# TeamB_PDS_Schematic_new.net
KiCad netlist of a schematic drawn in EAGLE
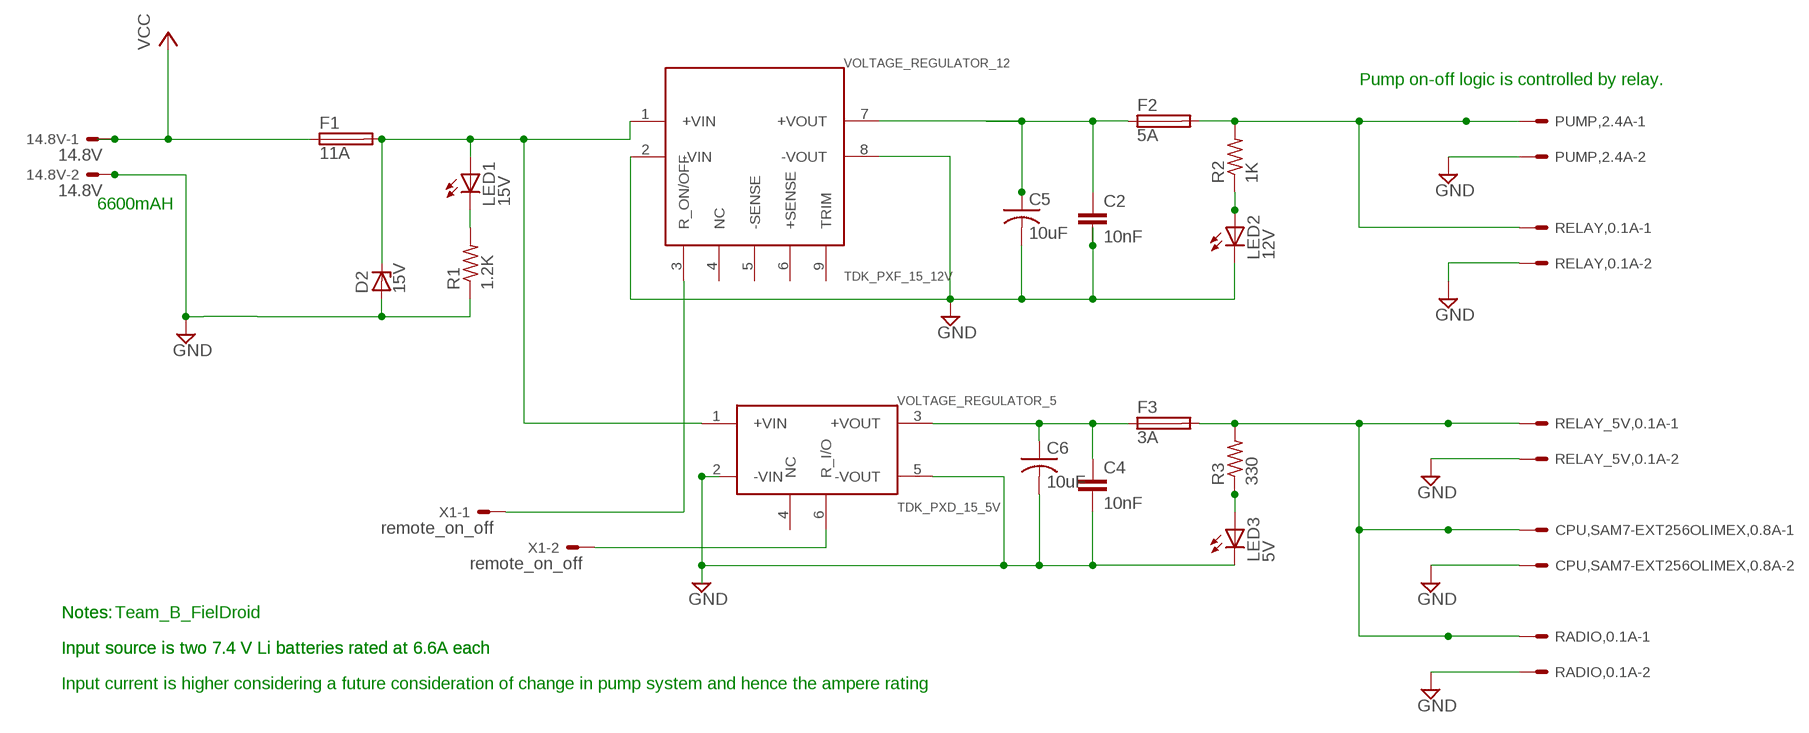
[diagram p0: schematic, sheet 1]

(export (version "E")
  (design (tool "Eeschema 10.0.6"))
  (components
    (comp (ref "14.8V")
      (value "14.8V")
      (footprint "eagle-import:5566-2")
      (libsource (lib "eagle-import") (part "5566-2"))
    )
    (comp (ref "C2")
      (value "10nF")
      (footprint "eagle-import:C2.5-4")
      (libsource (lib "eagle-import") (part "C2.5/4"))
    )
    (comp (ref "C4")
      (value "10nF")
      (footprint "eagle-import:C2.5-4")
      (libsource (lib "eagle-import") (part "C2.5/4"))
    )
    (comp (ref "C5")
      (value "10uF")
      (footprint "eagle-import:C050-045X075")
      (libsource (lib "eagle-import") (part "C-US050-045X075"))
    )
    (comp (ref "C6")
      (value "10uF")
      (footprint "eagle-import:C050-045X075")
      (libsource (lib "eagle-import") (part "C-US050-045X075"))
    )
    (comp (ref "CPU,SAM7-EXT256OLIMEX,0.8A")
      (value "5566-2")
      (footprint "eagle-import:5566-2")
      (libsource (lib "eagle-import") (part "5566-2"))
    )
    (comp (ref "D2")
      (value "15V")
      (footprint "eagle-import:DO41Z10")
      (libsource (lib "eagle-import") (part "1N4728"))
    )
    (comp (ref "F1")
      (value "11A")
      (footprint "eagle-import:FUSE_HOLDER_5X20MM")
      (libsource (lib "eagle-import") (part "FUSEBLANK_5X20MM"))
    )
    (comp (ref "F2")
      (value "5A")
      (footprint "eagle-import:FUSE_HOLDER_5X20MM")
      (libsource (lib "eagle-import") (part "FUSEBLANK_5X20MM"))
    )
    (comp (ref "F3")
      (value "3A")
      (footprint "eagle-import:FUSE_HOLDER_5X20MM")
      (libsource (lib "eagle-import") (part "FUSEBLANK_5X20MM"))
    )
    (comp (ref "LED1")
      (value "15V")
      (footprint "eagle-import:LED5MM")
      (libsource (lib "eagle-import") (part "LED5MM"))
    )
    (comp (ref "LED2")
      (value "12V")
      (footprint "eagle-import:LED5MM")
      (libsource (lib "eagle-import") (part "LED5MM"))
    )
    (comp (ref "LED3")
      (value "5V")
      (footprint "eagle-import:LED5MM")
      (libsource (lib "eagle-import") (part "LED5MM"))
    )
    (comp (ref "PUMP,2.4A")
      (value "5566-2")
      (footprint "eagle-import:5566-2")
      (libsource (lib "eagle-import") (part "5566-2"))
    )
    (comp (ref "R1")
      (value "1.2K")
      (footprint "eagle-import:0309_12")
      (libsource (lib "eagle-import") (part "R-US_0309/12"))
    )
    (comp (ref "R2")
      (value "1K")
      (footprint "eagle-import:0309_12")
      (libsource (lib "eagle-import") (part "R-US_0309/12"))
    )
    (comp (ref "R3")
      (value "330")
      (footprint "eagle-import:0309_12")
      (libsource (lib "eagle-import") (part "R-US_0309/12"))
    )
    (comp (ref "RADIO,0.1A")
      (value "5566-2")
      (footprint "eagle-import:5566-2")
      (libsource (lib "eagle-import") (part "5566-2"))
    )
    (comp (ref "RELAY,0.1A")
      (value "5566-2")
      (footprint "eagle-import:5566-2")
      (libsource (lib "eagle-import") (part "5566-2"))
    )
    (comp (ref "RELAY_5V,0.1A")
      (value "5566-2")
      (footprint "eagle-import:5566-2")
      (libsource (lib "eagle-import") (part "5566-2"))
    )
    (comp (ref "VOLTAGE_REGULATOR_5")
      (value "TDK_PXD_15_5V")
      (footprint "eagle-import:TDK-PXD_15-5V")
      (libsource (lib "eagle-import") (part "TDK_PXD_15_5V"))
    )
    (comp (ref "VOLTAGE_REGULATOR_12")
      (value "TDK_PXF_15_12V")
      (footprint "eagle-import:TDK_PXF_15_12V")
      (libsource (lib "eagle-import") (part "TDK_PXF_15_12V"))
    )
    (comp (ref "X1")
      (value "remote_on_off")
      (footprint "eagle-import:5566-2")
      (libsource (lib "eagle-import") (part "5566-2"))
    )
  )
  (nets
    (net (code "1") (name "GND") (class "Default")
      (node (ref "14.8V") (pin "2") (pinfunction "S_2") (pintype "passive"))
      (node (ref "C2") (pin "2") (pinfunction "2_2") (pintype "passive"))
      (node (ref "C4") (pin "2") (pinfunction "2_2") (pintype "passive"))
      (node (ref "C5") (pin "2") (pinfunction "2_2") (pintype "passive"))
      (node (ref "C6") (pin "2") (pinfunction "2_2") (pintype "passive"))
      (node (ref "CPU,SAM7-EXT256OLIMEX,0.8A") (pin "2") (pinfunction "S_2") (pintype "passive"))
      (node (ref "D2") (pin "A") (pinfunction "A_A") (pintype "passive"))
      (node (ref "LED2") (pin "K") (pinfunction "C_K") (pintype "passive"))
      (node (ref "LED3") (pin "K") (pinfunction "C_K") (pintype "passive"))
      (node (ref "PUMP,2.4A") (pin "2") (pinfunction "S_2") (pintype "passive"))
      (node (ref "R1") (pin "1") (pinfunction "1_1") (pintype "passive"))
      (node (ref "RADIO,0.1A") (pin "2") (pinfunction "S_2") (pintype "passive"))
      (node (ref "RELAY,0.1A") (pin "2") (pinfunction "S_2") (pintype "passive"))
      (node (ref "RELAY_5V,0.1A") (pin "2") (pinfunction "S_2") (pintype "passive"))
      (node (ref "VOLTAGE_REGULATOR_12") (pin "2") (pinfunction "-VIN_2") (pintype "bidirectional"))
      (node (ref "VOLTAGE_REGULATOR_12") (pin "8") (pinfunction "-VOUT_8") (pintype "bidirectional"))
      (node (ref "VOLTAGE_REGULATOR_5") (pin "2") (pinfunction "-VIN_2") (pintype "bidirectional"))
      (node (ref "VOLTAGE_REGULATOR_5") (pin "5") (pinfunction "-VOUT_5") (pintype "bidirectional"))
    )
    (net (code "2") (name "Net-(CPU,SAM7-EXT256OLIMEX,0.8AA-S)") (class "Default")
      (node (ref "CPU,SAM7-EXT256OLIMEX,0.8A") (pin "1") (pinfunction "S_1") (pintype "passive"))
      (node (ref "F3") (pin "2") (pinfunction "2_2") (pintype "passive"))
      (node (ref "R3") (pin "2") (pinfunction "2_2") (pintype "passive"))
      (node (ref "RADIO,0.1A") (pin "1") (pinfunction "S_1") (pintype "passive"))
      (node (ref "RELAY_5V,0.1A") (pin "1") (pinfunction "S_1") (pintype "passive"))
    )
    (net (code "3") (name "Net-(LED1-C)") (class "Default")
      (node (ref "LED1") (pin "K") (pinfunction "C_K") (pintype "passive"))
      (node (ref "R1") (pin "2") (pinfunction "2_2") (pintype "passive"))
    )
    (net (code "4") (name "Net-(LED2-PadA)") (class "Default")
      (node (ref "LED2") (pin "A") (pinfunction "A_A") (pintype "passive"))
      (node (ref "R2") (pin "1") (pinfunction "1_1") (pintype "passive"))
    )
    (net (code "5") (name "Net-(LED3-PadA)") (class "Default")
      (node (ref "LED3") (pin "A") (pinfunction "A_A") (pintype "passive"))
      (node (ref "R3") (pin "1") (pinfunction "1_1") (pintype "passive"))
    )
    (net (code "6") (name "Net-(PUMP,2.4AA-S)") (class "Default")
      (node (ref "F2") (pin "2") (pinfunction "2_2") (pintype "passive"))
      (node (ref "PUMP,2.4A") (pin "1") (pinfunction "S_1") (pintype "passive"))
      (node (ref "R2") (pin "2") (pinfunction "2_2") (pintype "passive"))
      (node (ref "RELAY,0.1A") (pin "1") (pinfunction "S_1") (pintype "passive"))
    )
    (net (code "7") (name "Net-(VOLTAGE_REGULATOR_5-+VOUT)") (class "Default")
      (node (ref "C4") (pin "1") (pinfunction "1_1") (pintype "passive"))
      (node (ref "C6") (pin "1") (pinfunction "1_1") (pintype "passive"))
      (node (ref "F3") (pin "1") (pinfunction "1_1") (pintype "passive"))
      (node (ref "VOLTAGE_REGULATOR_5") (pin "3") (pinfunction "+VOUT_3") (pintype "bidirectional"))
    )
    (net (code "8") (name "Net-(VOLTAGE_REGULATOR_5-R_I{slash}O)") (class "Default")
      (node (ref "VOLTAGE_REGULATOR_5") (pin "6") (pinfunction "R_I/O_6") (pintype "bidirectional"))
      (node (ref "X1") (pin "2") (pinfunction "S_2") (pintype "passive"))
    )
    (net (code "9") (name "Net-(VOLTAGE_REGULATOR_12-+VIN)") (class "Default")
      (node (ref "D2") (pin "C") (pinfunction "C_C") (pintype "passive"))
      (node (ref "F1") (pin "2") (pinfunction "2_2") (pintype "passive"))
      (node (ref "LED1") (pin "A") (pinfunction "A_A") (pintype "passive"))
      (node (ref "VOLTAGE_REGULATOR_12") (pin "1") (pinfunction "+VIN_1") (pintype "bidirectional"))
      (node (ref "VOLTAGE_REGULATOR_5") (pin "1") (pinfunction "+VIN_1") (pintype "bidirectional"))
    )
    (net (code "10") (name "Net-(VOLTAGE_REGULATOR_12-+VOUT)") (class "Default")
      (node (ref "C2") (pin "1") (pinfunction "1_1") (pintype "passive"))
      (node (ref "C5") (pin "1") (pinfunction "1_1") (pintype "passive"))
      (node (ref "F2") (pin "1") (pinfunction "1_1") (pintype "passive"))
      (node (ref "VOLTAGE_REGULATOR_12") (pin "7") (pinfunction "+VOUT_7") (pintype "bidirectional"))
    )
    (net (code "11") (name "Net-(VOLTAGE_REGULATOR_12-R_ON{slash}OFF)") (class "Default")
      (node (ref "VOLTAGE_REGULATOR_12") (pin "3") (pinfunction "R_ON/OFF_3") (pintype "bidirectional"))
      (node (ref "X1") (pin "1") (pinfunction "S_1") (pintype "passive"))
    )
    (net (code "12") (name "VCC") (class "Default")
      (node (ref "14.8V") (pin "1") (pinfunction "S_1") (pintype "passive"))
      (node (ref "F1") (pin "1") (pinfunction "1_1") (pintype "passive"))
    )
    (net (code "13") (name "unconnected-(VOLTAGE_REGULATOR_5-NC-Pad4)") (class "Default")
      (node (ref "VOLTAGE_REGULATOR_5") (pin "4") (pinfunction "NC_4") (pintype "no_connect"))
    )
    (net (code "14") (name "unconnected-(VOLTAGE_REGULATOR_12-+SENSE-Pad6)") (class "Default")
      (node (ref "VOLTAGE_REGULATOR_12") (pin "6") (pinfunction "+SENSE_6") (pintype "bidirectional"))
    )
    (net (code "15") (name "unconnected-(VOLTAGE_REGULATOR_12--SENSE-Pad5)") (class "Default")
      (node (ref "VOLTAGE_REGULATOR_12") (pin "5") (pinfunction "-SENSE_5") (pintype "bidirectional"))
    )
    (net (code "16") (name "unconnected-(VOLTAGE_REGULATOR_12-NC-Pad4)") (class "Default")
      (node (ref "VOLTAGE_REGULATOR_12") (pin "4") (pinfunction "NC_4") (pintype "no_connect"))
    )
    (net (code "17") (name "unconnected-(VOLTAGE_REGULATOR_12-TRIM-Pad9)") (class "Default")
      (node (ref "VOLTAGE_REGULATOR_12") (pin "9") (pinfunction "TRIM_9") (pintype "bidirectional"))
    )
  )
)
